# MRCS-Nano-Ard-Relay-Breakout.net
KiCad netlist of a schematic drawn in EAGLE
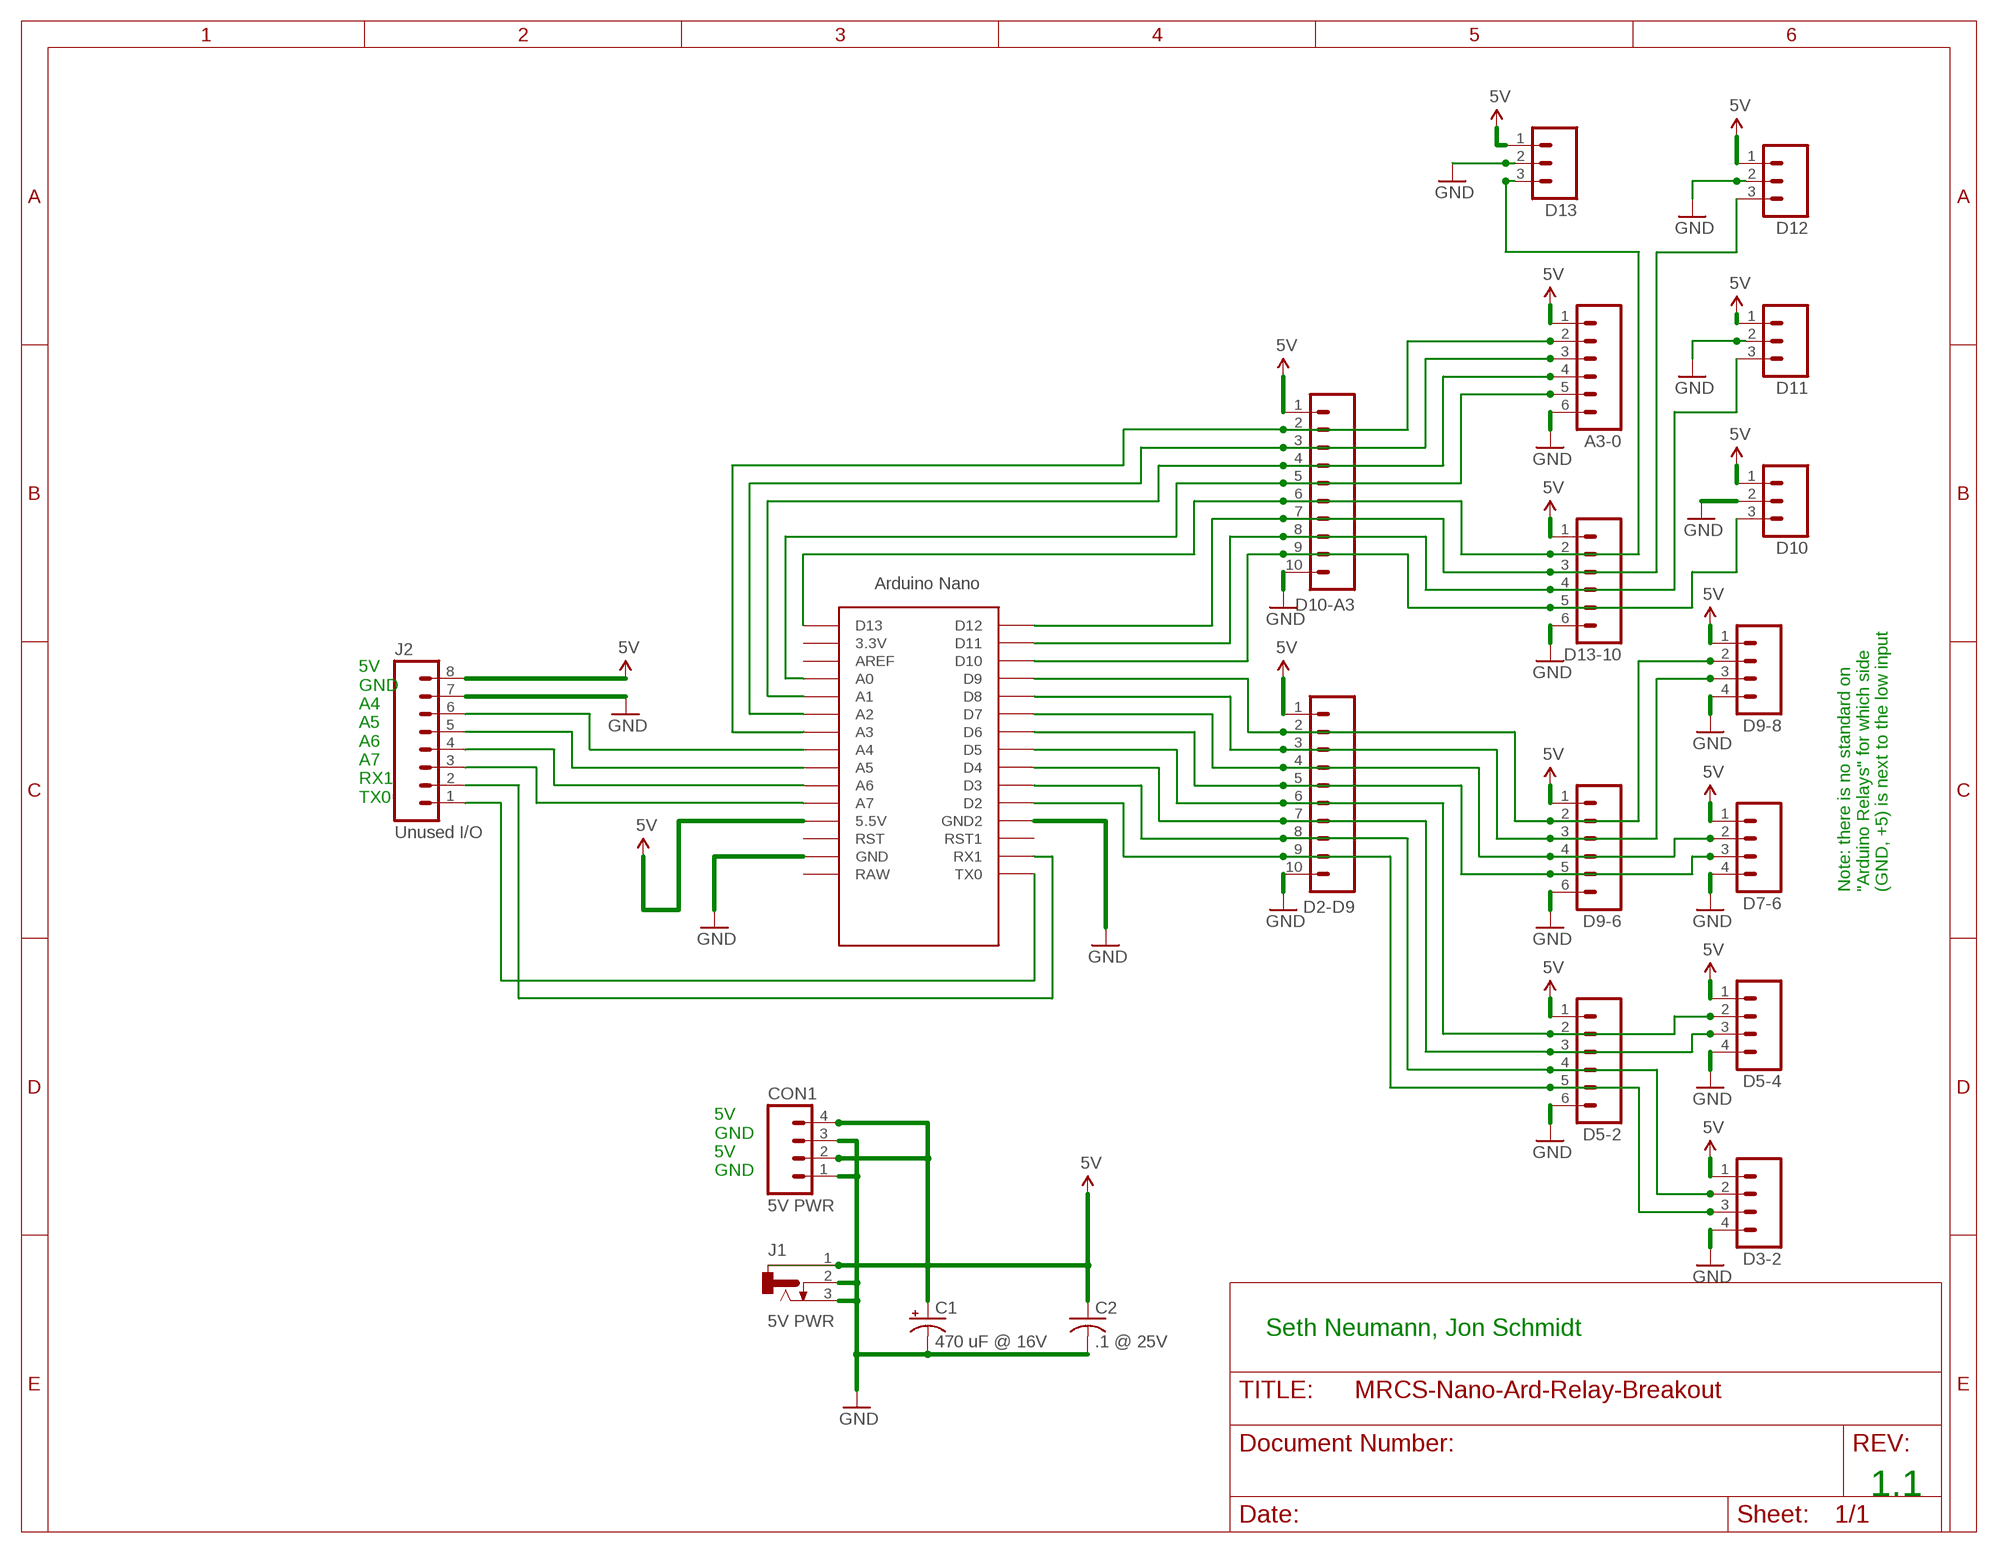
[diagram p0: schematic, sheet 1]

(export (version "E")
  (design (tool "Eeschema 10.0.6"))
  (components
    (comp (ref "A3-0")
      (value "CONNECTOR-M06LOCK")
      (footprint "eagle-import:1X06_LOCK")
      (libsource (lib "eagle-import") (part "CONNECTOR-M06LOCK"))
    )
    (comp (ref "C1")
      (value "470 uF @ 16V")
      (footprint "eagle-import:E3.5-10")
      (libsource (lib "eagle-import") (part "CAP-POLPTH-3.5MM"))
    )
    (comp (ref "C2")
      (value ".1 @ 25V")
      (footprint "eagle-import:C-PTH-0.100")
      (libsource (lib "eagle-import") (part "CAPPTH2"))
    )
    (comp (ref "CON1")
      (value "5V PWR")
      (footprint "eagle-import:SCREWTERMINAL-3.5MM-4_LOCK")
      (libsource (lib "eagle-import") (part "CONNECTOR-M04SCREW_LOCK"))
    )
    (comp (ref "D2-D9")
      (value "CONNECTOR-M10LOCK")
      (footprint "eagle-import:1X10_LOCK")
      (libsource (lib "eagle-import") (part "CONNECTOR-M10LOCK"))
    )
    (comp (ref "D3-2")
      (value "CONNECTOR-M04LOCK")
      (footprint "eagle-import:1X04_LOCK")
      (libsource (lib "eagle-import") (part "CONNECTOR-M04LOCK"))
    )
    (comp (ref "D5-2")
      (value "CONNECTOR-M06LOCK")
      (footprint "eagle-import:1X06_LOCK")
      (libsource (lib "eagle-import") (part "CONNECTOR-M06LOCK"))
    )
    (comp (ref "D5-4")
      (value "CONNECTOR-M04LOCK")
      (footprint "eagle-import:1X04_LOCK")
      (libsource (lib "eagle-import") (part "CONNECTOR-M04LOCK"))
    )
    (comp (ref "D7-6")
      (value "CONNECTOR-M04LOCK")
      (footprint "eagle-import:1X04_LOCK")
      (libsource (lib "eagle-import") (part "CONNECTOR-M04LOCK"))
    )
    (comp (ref "D9-6")
      (value "CONNECTOR-M06LOCK")
      (footprint "eagle-import:1X06_LOCK")
      (libsource (lib "eagle-import") (part "CONNECTOR-M06LOCK"))
    )
    (comp (ref "D9-8")
      (value "CONNECTOR-M04LOCK")
      (footprint "eagle-import:1X04_LOCK")
      (libsource (lib "eagle-import") (part "CONNECTOR-M04LOCK"))
    )
    (comp (ref "D10")
      (value "CONNECTOR-M03MOLEX-254-LOCK")
      (footprint "eagle-import:MOLEX-1X3_LOCK")
      (libsource (lib "eagle-import") (part "CONNECTOR-M03MOLEX-254-LOCK"))
    )
    (comp (ref "D10-A3")
      (value "CONNECTOR-M10LOCK")
      (footprint "eagle-import:1X10_LOCK")
      (libsource (lib "eagle-import") (part "CONNECTOR-M10LOCK"))
    )
    (comp (ref "D11")
      (value "CONNECTOR-M03MOLEX-254-LOCK")
      (footprint "eagle-import:MOLEX-1X3_LOCK")
      (libsource (lib "eagle-import") (part "CONNECTOR-M03MOLEX-254-LOCK"))
    )
    (comp (ref "D12")
      (value "CONNECTOR-M03MOLEX-254-LOCK")
      (footprint "eagle-import:MOLEX-1X3_LOCK")
      (libsource (lib "eagle-import") (part "CONNECTOR-M03MOLEX-254-LOCK"))
    )
    (comp (ref "D13")
      (value "CONNECTOR-M03MOLEX-254-LOCK")
      (footprint "eagle-import:MOLEX-1X3_LOCK")
      (libsource (lib "eagle-import") (part "CONNECTOR-M03MOLEX-254-LOCK"))
    )
    (comp (ref "D13-10")
      (value "CONNECTOR-M06LOCK")
      (footprint "eagle-import:1X06_LOCK")
      (libsource (lib "eagle-import") (part "CONNECTOR-M06LOCK"))
    )
    (comp (ref "J1")
      (value "5V PWR")
      (footprint "eagle-import:DCJ0202")
      (libsource (lib "eagle-import") (part "CONNECTOR-DC-POWER-RA"))
    )
    (comp (ref "J2")
      (value "Unused I/O")
      (footprint "eagle-import:1X08_LOCK")
      (libsource (lib "eagle-import") (part "CONNECTOR-M08LOCK"))
    )
    (comp (ref "U$1")
      (value "NANO")
      (footprint "eagle-import:NANO")
      (libsource (lib "eagle-import") (part "NANO"))
    )
  )
  (nets
    (net (code "1") (name "5V") (class "Default")
      (node (ref "A3-0") (pin "1") (pinfunction "1_1") (pintype "passive"))
      (node (ref "C1") (pin "+") (pinfunction "+_+") (pintype "passive"))
      (node (ref "C2") (pin "1") (pinfunction "1_1") (pintype "passive"))
      (node (ref "CON1") (pin "2") (pinfunction "2_2") (pintype "passive"))
      (node (ref "CON1") (pin "4") (pinfunction "4_4") (pintype "passive"))
      (node (ref "D10") (pin "1") (pinfunction "1_1") (pintype "passive"))
      (node (ref "D10-A3") (pin "1") (pinfunction "1_1") (pintype "passive"))
      (node (ref "D11") (pin "1") (pinfunction "1_1") (pintype "passive"))
      (node (ref "D12") (pin "1") (pinfunction "1_1") (pintype "passive"))
      (node (ref "D13") (pin "1") (pinfunction "1_1") (pintype "passive"))
      (node (ref "D13-10") (pin "1") (pinfunction "1_1") (pintype "passive"))
      (node (ref "D2-D9") (pin "1") (pinfunction "1_1") (pintype "passive"))
      (node (ref "D3-2") (pin "1") (pinfunction "1_1") (pintype "passive"))
      (node (ref "D5-2") (pin "1") (pinfunction "1_1") (pintype "passive"))
      (node (ref "D5-4") (pin "1") (pinfunction "1_1") (pintype "passive"))
      (node (ref "D7-6") (pin "1") (pinfunction "1_1") (pintype "passive"))
      (node (ref "D9-6") (pin "1") (pinfunction "1_1") (pintype "passive"))
      (node (ref "D9-8") (pin "1") (pinfunction "1_1") (pintype "passive"))
      (node (ref "J1") (pin "1") (pinfunction "1_1") (pintype "passive"))
      (node (ref "J2") (pin "8") (pinfunction "8_8") (pintype "passive"))
      (node (ref "U$1") (pin "5V") (pinfunction "5.5V_5V") (pintype "bidirectional"))
    )
    (net (code "2") (name "GND") (class "Default")
      (node (ref "A3-0") (pin "6") (pinfunction "6_6") (pintype "passive"))
      (node (ref "C1") (pin "-") (pinfunction "-_-") (pintype "passive"))
      (node (ref "C2") (pin "2") (pinfunction "2_2") (pintype "passive"))
      (node (ref "CON1") (pin "1") (pinfunction "1_1") (pintype "passive"))
      (node (ref "CON1") (pin "3") (pinfunction "3_3") (pintype "passive"))
      (node (ref "D10") (pin "2") (pinfunction "2_2") (pintype "passive"))
      (node (ref "D10-A3") (pin "10") (pinfunction "10_10") (pintype "passive"))
      (node (ref "D11") (pin "2") (pinfunction "2_2") (pintype "passive"))
      (node (ref "D12") (pin "2") (pinfunction "2_2") (pintype "passive"))
      (node (ref "D13") (pin "2") (pinfunction "2_2") (pintype "passive"))
      (node (ref "D13-10") (pin "6") (pinfunction "6_6") (pintype "passive"))
      (node (ref "D2-D9") (pin "10") (pinfunction "10_10") (pintype "passive"))
      (node (ref "D3-2") (pin "4") (pinfunction "4_4") (pintype "passive"))
      (node (ref "D5-2") (pin "6") (pinfunction "6_6") (pintype "passive"))
      (node (ref "D5-4") (pin "4") (pinfunction "4_4") (pintype "passive"))
      (node (ref "D7-6") (pin "4") (pinfunction "4_4") (pintype "passive"))
      (node (ref "D9-6") (pin "6") (pinfunction "6_6") (pintype "passive"))
      (node (ref "D9-8") (pin "4") (pinfunction "4_4") (pintype "passive"))
      (node (ref "J1") (pin "2") (pinfunction "2_2") (pintype "passive"))
      (node (ref "J1") (pin "3") (pinfunction "3_3") (pintype "passive"))
      (node (ref "J2") (pin "7") (pinfunction "7_7") (pintype "passive"))
      (node (ref "U$1") (pin "GND") (pinfunction "GND_GND") (pintype "bidirectional"))
      (node (ref "U$1") (pin "GND1") (pinfunction "GND2_GND1") (pintype "bidirectional"))
    )
    (net (code "3") (name "Net-(A3-0-Pad2)") (class "Default")
      (node (ref "A3-0") (pin "2") (pinfunction "2_2") (pintype "passive"))
      (node (ref "D10-A3") (pin "2") (pinfunction "2_2") (pintype "passive"))
      (node (ref "U$1") (pin "A3") (pinfunction "A3_A3") (pintype "bidirectional"))
    )
    (net (code "4") (name "Net-(A3-0-Pad3)") (class "Default")
      (node (ref "A3-0") (pin "3") (pinfunction "3_3") (pintype "passive"))
      (node (ref "D10-A3") (pin "3") (pinfunction "3_3") (pintype "passive"))
      (node (ref "U$1") (pin "A2") (pinfunction "A2_A2") (pintype "bidirectional"))
    )
    (net (code "5") (name "Net-(A3-0-Pad4)") (class "Default")
      (node (ref "A3-0") (pin "4") (pinfunction "4_4") (pintype "passive"))
      (node (ref "D10-A3") (pin "4") (pinfunction "4_4") (pintype "passive"))
      (node (ref "U$1") (pin "A1") (pinfunction "A1_A1") (pintype "bidirectional"))
    )
    (net (code "6") (name "Net-(A3-0-Pad5)") (class "Default")
      (node (ref "A3-0") (pin "5") (pinfunction "5_5") (pintype "passive"))
      (node (ref "D10-A3") (pin "5") (pinfunction "5_5") (pintype "passive"))
      (node (ref "U$1") (pin "A0") (pinfunction "A0_A0") (pintype "bidirectional"))
    )
    (net (code "7") (name "Net-(D2-D9-Pad2)") (class "Default")
      (node (ref "D2-D9") (pin "2") (pinfunction "2_2") (pintype "passive"))
      (node (ref "D9-6") (pin "2") (pinfunction "2_2") (pintype "passive"))
      (node (ref "D9-8") (pin "2") (pinfunction "2_2") (pintype "passive"))
      (node (ref "U$1") (pin "D9") (pinfunction "D9_D9") (pintype "bidirectional"))
    )
    (net (code "8") (name "Net-(D2-D9-Pad3)") (class "Default")
      (node (ref "D2-D9") (pin "3") (pinfunction "3_3") (pintype "passive"))
      (node (ref "D9-6") (pin "3") (pinfunction "3_3") (pintype "passive"))
      (node (ref "D9-8") (pin "3") (pinfunction "3_3") (pintype "passive"))
      (node (ref "U$1") (pin "D8") (pinfunction "D8_D8") (pintype "bidirectional"))
    )
    (net (code "9") (name "Net-(D2-D9-Pad4)") (class "Default")
      (node (ref "D2-D9") (pin "4") (pinfunction "4_4") (pintype "passive"))
      (node (ref "D7-6") (pin "2") (pinfunction "2_2") (pintype "passive"))
      (node (ref "D9-6") (pin "4") (pinfunction "4_4") (pintype "passive"))
      (node (ref "U$1") (pin "D7") (pinfunction "D7_D7") (pintype "bidirectional"))
    )
    (net (code "10") (name "Net-(D2-D9-Pad5)") (class "Default")
      (node (ref "D2-D9") (pin "5") (pinfunction "5_5") (pintype "passive"))
      (node (ref "D7-6") (pin "3") (pinfunction "3_3") (pintype "passive"))
      (node (ref "D9-6") (pin "5") (pinfunction "5_5") (pintype "passive"))
      (node (ref "U$1") (pin "D6") (pinfunction "D6_D6") (pintype "bidirectional"))
    )
    (net (code "11") (name "Net-(D2-D9-Pad6)") (class "Default")
      (node (ref "D2-D9") (pin "6") (pinfunction "6_6") (pintype "passive"))
      (node (ref "D5-2") (pin "2") (pinfunction "2_2") (pintype "passive"))
      (node (ref "D5-4") (pin "2") (pinfunction "2_2") (pintype "passive"))
      (node (ref "U$1") (pin "D5") (pinfunction "D5_D5") (pintype "bidirectional"))
    )
    (net (code "12") (name "Net-(D2-D9-Pad7)") (class "Default")
      (node (ref "D2-D9") (pin "7") (pinfunction "7_7") (pintype "passive"))
      (node (ref "D5-2") (pin "3") (pinfunction "3_3") (pintype "passive"))
      (node (ref "D5-4") (pin "3") (pinfunction "3_3") (pintype "passive"))
      (node (ref "U$1") (pin "D4") (pinfunction "D4_D4") (pintype "bidirectional"))
    )
    (net (code "13") (name "Net-(D2-D9-Pad8)") (class "Default")
      (node (ref "D2-D9") (pin "8") (pinfunction "8_8") (pintype "passive"))
      (node (ref "D3-2") (pin "2") (pinfunction "2_2") (pintype "passive"))
      (node (ref "D5-2") (pin "4") (pinfunction "4_4") (pintype "passive"))
      (node (ref "U$1") (pin "D3") (pinfunction "D3_D3") (pintype "bidirectional"))
    )
    (net (code "14") (name "Net-(D2-D9-Pad9)") (class "Default")
      (node (ref "D2-D9") (pin "9") (pinfunction "9_9") (pintype "passive"))
      (node (ref "D3-2") (pin "3") (pinfunction "3_3") (pintype "passive"))
      (node (ref "D5-2") (pin "5") (pinfunction "5_5") (pintype "passive"))
      (node (ref "U$1") (pin "D2") (pinfunction "D2_D2") (pintype "bidirectional"))
    )
    (net (code "15") (name "Net-(D10-A3-Pad6)") (class "Default")
      (node (ref "D10-A3") (pin "6") (pinfunction "6_6") (pintype "passive"))
      (node (ref "D13") (pin "3") (pinfunction "3_3") (pintype "passive"))
      (node (ref "D13-10") (pin "2") (pinfunction "2_2") (pintype "passive"))
      (node (ref "U$1") (pin "D13") (pinfunction "D13_D13") (pintype "bidirectional"))
    )
    (net (code "16") (name "Net-(D10-A3-Pad7)") (class "Default")
      (node (ref "D10-A3") (pin "7") (pinfunction "7_7") (pintype "passive"))
      (node (ref "D12") (pin "3") (pinfunction "3_3") (pintype "passive"))
      (node (ref "D13-10") (pin "3") (pinfunction "3_3") (pintype "passive"))
      (node (ref "U$1") (pin "D12") (pinfunction "D12_D12") (pintype "bidirectional"))
    )
    (net (code "17") (name "Net-(D10-A3-Pad8)") (class "Default")
      (node (ref "D10-A3") (pin "8") (pinfunction "8_8") (pintype "passive"))
      (node (ref "D11") (pin "3") (pinfunction "3_3") (pintype "passive"))
      (node (ref "D13-10") (pin "4") (pinfunction "4_4") (pintype "passive"))
      (node (ref "U$1") (pin "D11") (pinfunction "D11_D11") (pintype "bidirectional"))
    )
    (net (code "18") (name "Net-(D10-A3-Pad9)") (class "Default")
      (node (ref "D10") (pin "3") (pinfunction "3_3") (pintype "passive"))
      (node (ref "D10-A3") (pin "9") (pinfunction "9_9") (pintype "passive"))
      (node (ref "D13-10") (pin "5") (pinfunction "5_5") (pintype "passive"))
      (node (ref "U$1") (pin "D10") (pinfunction "D10_D10") (pintype "bidirectional"))
    )
    (net (code "19") (name "Net-(J2-Pad1)") (class "Default")
      (node (ref "J2") (pin "1") (pinfunction "1_1") (pintype "passive"))
      (node (ref "U$1") (pin "TX0") (pinfunction "TX0_TX0") (pintype "bidirectional"))
    )
    (net (code "20") (name "Net-(J2-Pad2)") (class "Default")
      (node (ref "J2") (pin "2") (pinfunction "2_2") (pintype "passive"))
      (node (ref "U$1") (pin "RX1") (pinfunction "RX1_RX1") (pintype "bidirectional"))
    )
    (net (code "21") (name "Net-(J2-Pad3)") (class "Default")
      (node (ref "J2") (pin "3") (pinfunction "3_3") (pintype "passive"))
      (node (ref "U$1") (pin "A7") (pinfunction "A7_A7") (pintype "bidirectional"))
    )
    (net (code "22") (name "Net-(J2-Pad4)") (class "Default")
      (node (ref "J2") (pin "4") (pinfunction "4_4") (pintype "passive"))
      (node (ref "U$1") (pin "A6") (pinfunction "A6_A6") (pintype "bidirectional"))
    )
    (net (code "23") (name "Net-(J2-Pad5)") (class "Default")
      (node (ref "J2") (pin "5") (pinfunction "5_5") (pintype "passive"))
      (node (ref "U$1") (pin "A5") (pinfunction "A5_A5") (pintype "bidirectional"))
    )
    (net (code "24") (name "Net-(J2-Pad6)") (class "Default")
      (node (ref "J2") (pin "6") (pinfunction "6_6") (pintype "passive"))
      (node (ref "U$1") (pin "A4") (pinfunction "A4_A4") (pintype "bidirectional"))
    )
    (net (code "25") (name "unconnected-(U$1-Pad3.3V)") (class "Default")
      (node (ref "U$1") (pin "3.3V") (pinfunction "3.3V_3.3V") (pintype "bidirectional"))
    )
    (net (code "26") (name "unconnected-(U$1-PadAREF)") (class "Default")
      (node (ref "U$1") (pin "AREF") (pinfunction "AREF_AREF") (pintype "bidirectional"))
    )
    (net (code "27") (name "unconnected-(U$1-PadRAW)") (class "Default")
      (node (ref "U$1") (pin "RAW") (pinfunction "RAW_RAW") (pintype "bidirectional"))
    )
    (net (code "28") (name "unconnected-(U$1-PadRST)") (class "Default")
      (node (ref "U$1") (pin "RST") (pinfunction "RST_RST") (pintype "bidirectional"))
    )
    (net (code "29") (name "unconnected-(U$1-PadRST1)") (class "Default")
      (node (ref "U$1") (pin "RST1") (pinfunction "RST1_RST1") (pintype "bidirectional"))
    )
  )
)
